# USB2_0.net
KiCad netlist of a schematic drawn in Altium Designer
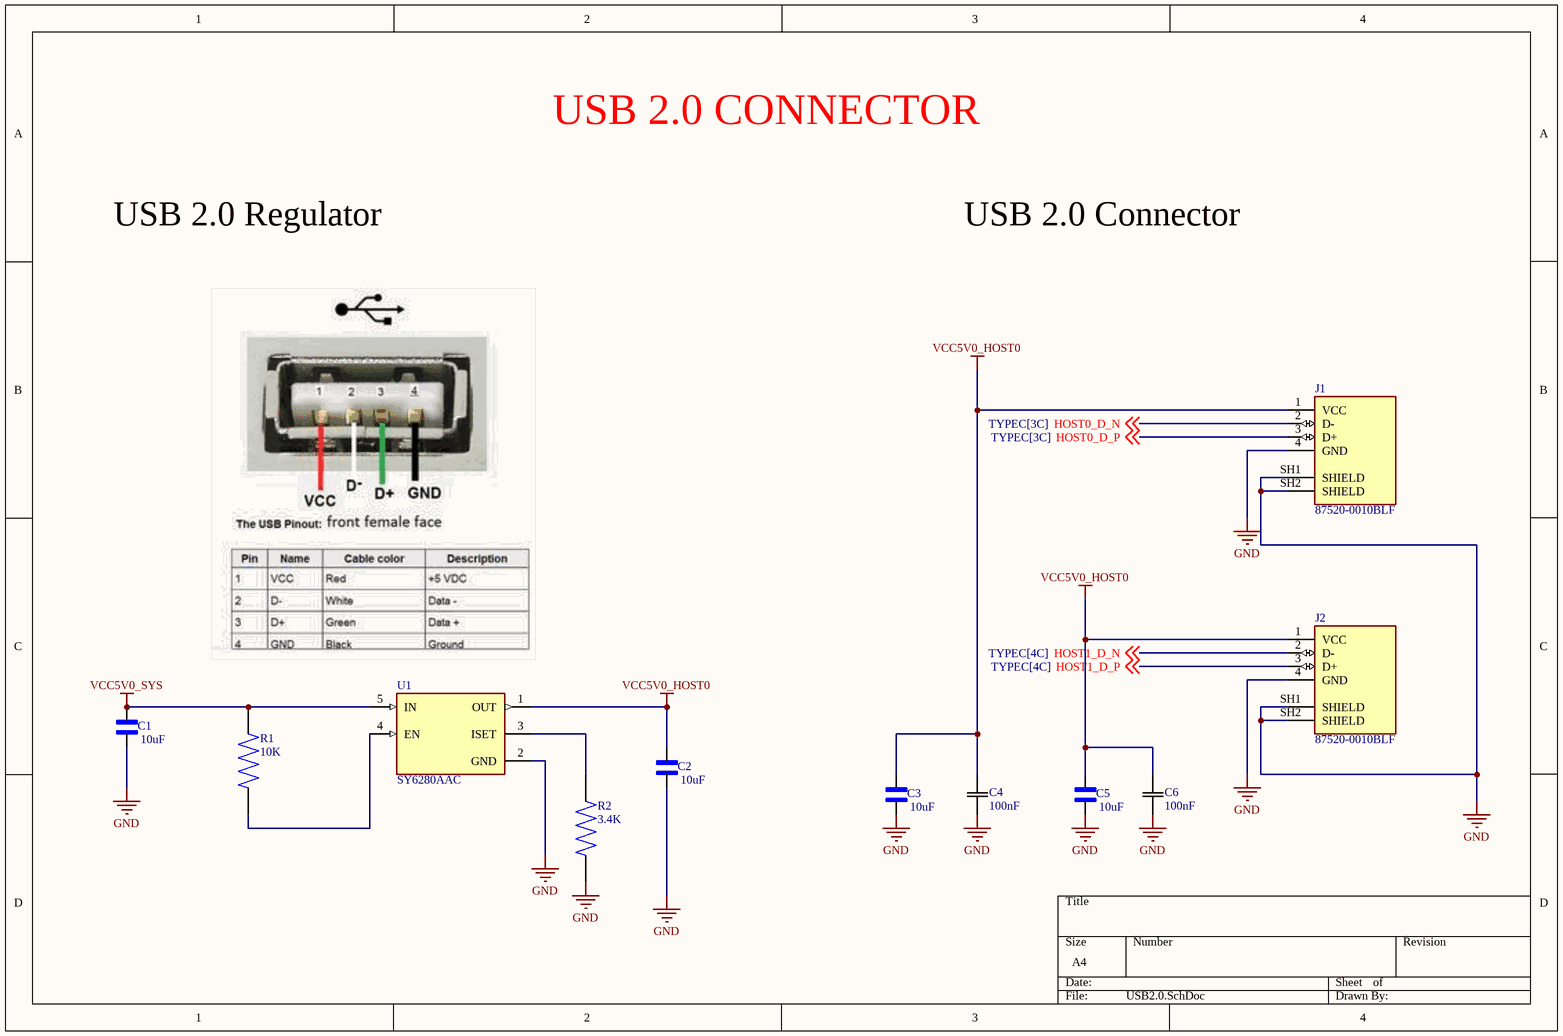
[diagram p0: USB2.0.SchDoc]

(export (version "E")
  (design (tool "Eeschema 10.0.6"))
  (components
    (comp (ref "C1")
      (value "10uF")
      (footprint "CAPC1005X70N")
      (description "10 ÂµF Â±20% 6.3V Ceramic Capacitor X5R 0402 (1005 Metric)")
      (fields (field (name "MF") "Samsung") (field (name "MP") "CL05A106MQ5NUNC"))
      (libsource (lib "CL05A106MQ5NUNC") (part "CL05A106MQ5NUNC"))
    )
    (comp (ref "C2")
      (value "10uF")
      (footprint "CAPC1005X70N")
      (description "10 ÂµF Â±20% 6.3V Ceramic Capacitor X5R 0402 (1005 Metric)")
      (fields (field (name "MF") "Samsung") (field (name "MP") "CL05A106MQ5NUNC"))
      (libsource (lib "CL05A106MQ5NUNC") (part "CL05A106MQ5NUNC"))
    )
    (comp (ref "C3")
      (value "10uF")
      (footprint "CAPC1005X70N")
      (description "10 ÂµF Â±20% 6.3V Ceramic Capacitor X5R 0402 (1005 Metric)")
      (fields (field (name "MF") "Samsung") (field (name "MP") "CL05A106MQ5NUNC"))
      (libsource (lib "CL05A106MQ5NUNC") (part "CL05A106MQ5NUNC"))
    )
    (comp (ref "C4")
      (value "100nF")
      (footprint "CAP_1005_TDK")
      (description "Description")
      (fields
        (field (name "MANUFACTURER_PART_NUMBER") "C1005X7R1H104M050BB")
        (field (name "COPYRIGHT") "Copyright (C) 2025 Ultra Librarian. All rights reserved.")
      )
      (libsource (lib "C1005X7R1H104M050BB") (part "C1005X7R1H104M050BB"))
    )
    (comp (ref "C5")
      (value "10uF")
      (footprint "CAPC1005X70N")
      (description "10 ÂµF Â±20% 6.3V Ceramic Capacitor X5R 0402 (1005 Metric)")
      (fields (field (name "MF") "Samsung") (field (name "MP") "CL05A106MQ5NUNC"))
      (libsource (lib "CL05A106MQ5NUNC") (part "CL05A106MQ5NUNC"))
    )
    (comp (ref "C6")
      (value "100nF")
      (footprint "CAP_1005_TDK")
      (description "Description")
      (fields
        (field (name "MANUFACTURER_PART_NUMBER") "C1005X7R1H104M050BB")
        (field (name "COPYRIGHT") "Copyright (C) 2025 Ultra Librarian. All rights reserved.")
      )
      (libsource (lib "C1005X7R1H104M050BB") (part "C1005X7R1H104M050BB"))
    )
    (comp (ref "J1")
      (value "87520-0010BLF")
      (footprint "AMPHENOL_87520-0010BLF")
      (fields (field (name "MF") "AMPHENOL ICC / FCI"))
      (libsource (lib "87520-0010BLF") (part "87520-0010BLF"))
    )
    (comp (ref "J2")
      (value "87520-0010BLF")
      (footprint "AMPHENOL_87520-0010BLF")
      (fields (field (name "MF") "AMPHENOL ICC / FCI"))
      (libsource (lib "87520-0010BLF") (part "87520-0010BLF"))
    )
    (comp (ref "R1")
      (value "10K")
      (footprint "RES_ERA3ARB103V")
      (fields (field (name "MP") "ERA3ARB103V"))
      (libsource (lib "ERA3ARB103V") (part "ERA3ARB103V"))
    )
    (comp (ref "R2")
      (value "3.4K")
      (footprint "RES_ERJPA2F3401X")
      (fields (field (name "MP") "ERJPA2F3401X"))
      (libsource (lib "ERJPA2F3401X") (part "ERJPA2F3401X"))
    )
    (comp (ref "U1")
      (value "SY6280AAC")
      (footprint "SOT95P285X130-5N")
      (description "USB Power Distribution SW Single 5.5V 1A 5-Pin SOT-23")
      (fields (field (name "MF") "Silergy"))
      (libsource (lib "SY6280AAC") (part "SY6280AAC"))
    )
  )
  (nets
    (net (code "1") (name "GND") (class "Default")
      (node (ref "C1") (pin "1") (pinfunction "1_1") (pintype "passive"))
      (node (ref "C2") (pin "1") (pinfunction "1_1") (pintype "passive"))
      (node (ref "C3") (pin "1") (pinfunction "1_1") (pintype "passive"))
      (node (ref "C4") (pin "2") (pinfunction "2_2") (pintype "passive"))
      (node (ref "C5") (pin "1") (pinfunction "1_1") (pintype "passive"))
      (node (ref "C6") (pin "2") (pinfunction "2_2") (pintype "passive"))
      (node (ref "J1") (pin "4") (pinfunction "GND_4") (pintype "power_in"))
      (node (ref "J1") (pin "SH1") (pinfunction "SHIELD_SH1") (pintype "passive"))
      (node (ref "J1") (pin "SH2") (pinfunction "SHIELD_SH2") (pintype "passive"))
      (node (ref "J2") (pin "4") (pinfunction "GND_4") (pintype "power_in"))
      (node (ref "J2") (pin "SH1") (pinfunction "SHIELD_SH1") (pintype "passive"))
      (node (ref "J2") (pin "SH2") (pinfunction "SHIELD_SH2") (pintype "passive"))
      (node (ref "R2") (pin "1") (pinfunction "1_1") (pintype "passive"))
      (node (ref "U1") (pin "2") (pinfunction "GND_2") (pintype "power_in"))
    )
    (net (code "2") (name "HOST0_D_N") (class "Default")
      (node (ref "J1") (pin "2") (pinfunction "D-_2") (pintype "bidirectional"))
    )
    (net (code "3") (name "HOST0_D_P") (class "Default")
      (node (ref "J1") (pin "3") (pinfunction "D+_3") (pintype "bidirectional"))
    )
    (net (code "4") (name "HOST1_D_N") (class "Default")
      (node (ref "J2") (pin "2") (pinfunction "D-_2") (pintype "bidirectional"))
    )
    (net (code "5") (name "HOST1_D_P") (class "Default")
      (node (ref "J2") (pin "3") (pinfunction "D+_3") (pintype "bidirectional"))
    )
    (net (code "6") (name "Net-(U1-EN)") (class "Default")
      (node (ref "R1") (pin "1") (pinfunction "1_1") (pintype "passive"))
      (node (ref "U1") (pin "4") (pinfunction "EN_4") (pintype "input"))
    )
    (net (code "7") (name "Net-(U1-ISET)") (class "Default")
      (node (ref "R2") (pin "2") (pinfunction "2_2") (pintype "passive"))
      (node (ref "U1") (pin "3") (pinfunction "ISET_3") (pintype "passive"))
    )
    (net (code "8") (name "VCC5V0_HOST0") (class "Default")
      (node (ref "C2") (pin "2") (pinfunction "2_2") (pintype "passive"))
      (node (ref "C3") (pin "2") (pinfunction "2_2") (pintype "passive"))
      (node (ref "C4") (pin "1") (pinfunction "1_1") (pintype "passive"))
      (node (ref "C5") (pin "2") (pinfunction "2_2") (pintype "passive"))
      (node (ref "C6") (pin "1") (pinfunction "1_1") (pintype "passive"))
      (node (ref "J1") (pin "1") (pinfunction "VCC_1") (pintype "power_in"))
      (node (ref "J2") (pin "1") (pinfunction "VCC_1") (pintype "power_in"))
      (node (ref "U1") (pin "1") (pinfunction "OUT_1") (pintype "output"))
    )
    (net (code "9") (name "VCC5V0_SYS") (class "Default")
      (node (ref "C1") (pin "2") (pinfunction "2_2") (pintype "passive"))
      (node (ref "R1") (pin "2") (pinfunction "2_2") (pintype "passive"))
      (node (ref "U1") (pin "5") (pinfunction "IN_5") (pintype "input"))
    )
  )
)
